# U_LEDs_I2C_PORT.net
KiCad netlist of a schematic drawn in Altium Designer
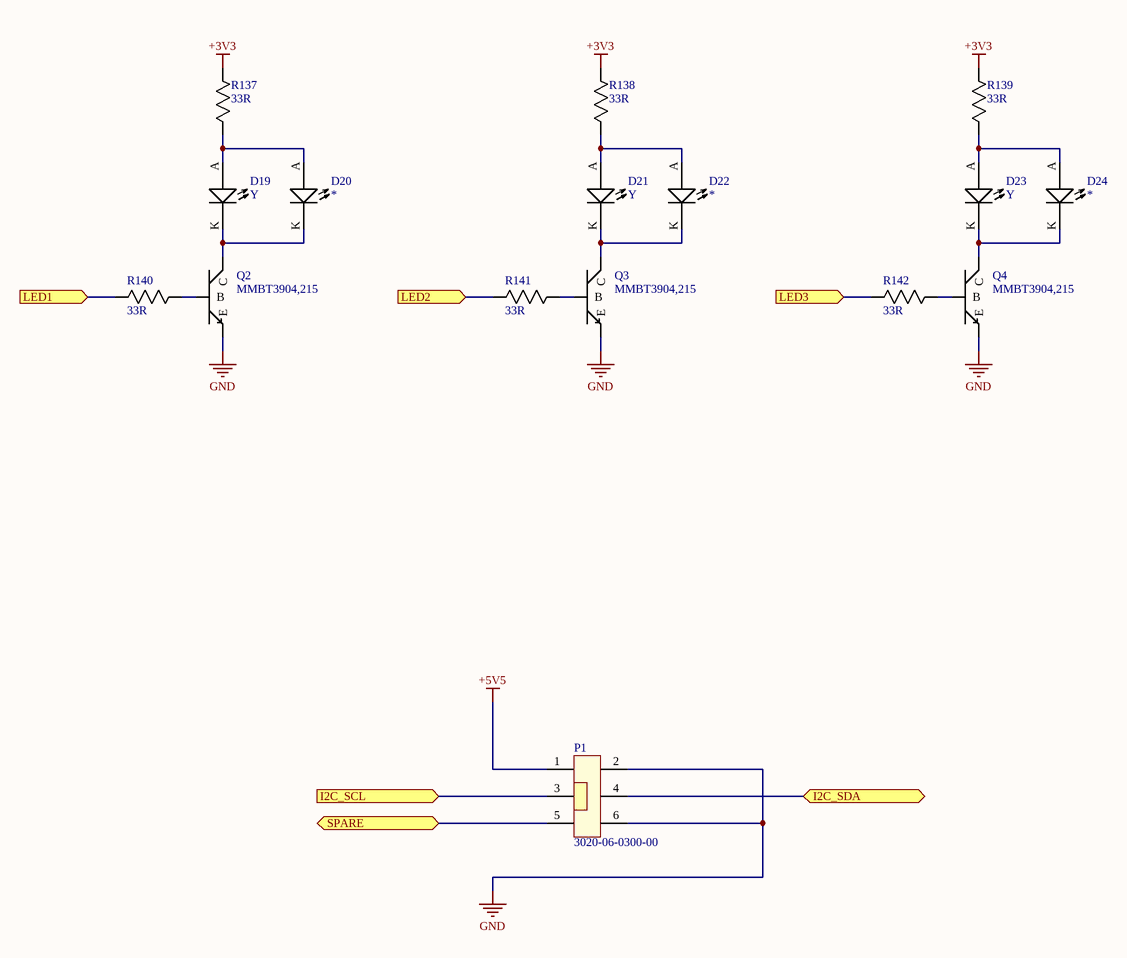
[diagram p0: U_LEDs_I2C_PORT.SchDoc]

(export (version "E")
  (design (tool "Eeschema 10.0.6"))
  (components
    (comp (ref "D19")
      (value "Diode_LED")
      (footprint "0805_LED")
      (description "LED")
      (fields (field (name "MFG") "Osram") (field (name "TYPE") "Y"))
      (libsource (lib "ADAPTONE_CARTE_DE_SON") (part "Diode_LED"))
    )
    (comp (ref "D20")
      (value "Diode_LED")
      (footprint "0805_LED")
      (description "LED")
      (fields (field (name "MFG") "Osram") (field (name "NI") "*"))
      (libsource (lib "ADAPTONE_CARTE_DE_SON") (part "Diode_LED"))
    )
    (comp (ref "D21")
      (value "Diode_LED")
      (footprint "0805_LED")
      (description "LED")
      (fields (field (name "MFG") "Osram") (field (name "TYPE") "Y"))
      (libsource (lib "ADAPTONE_CARTE_DE_SON") (part "Diode_LED"))
    )
    (comp (ref "D22")
      (value "Diode_LED")
      (footprint "0805_LED")
      (description "LED")
      (fields (field (name "MFG") "Osram") (field (name "NI") "*"))
      (libsource (lib "ADAPTONE_CARTE_DE_SON") (part "Diode_LED"))
    )
    (comp (ref "D23")
      (value "Diode_LED")
      (footprint "0805_LED")
      (description "LED")
      (fields (field (name "MFG") "Osram") (field (name "TYPE") "Y"))
      (libsource (lib "ADAPTONE_CARTE_DE_SON") (part "Diode_LED"))
    )
    (comp (ref "D24")
      (value "Diode_LED")
      (footprint "0805_LED")
      (description "LED")
      (fields (field (name "MFG") "Osram") (field (name "NI") "*"))
      (libsource (lib "ADAPTONE_CARTE_DE_SON") (part "Diode_LED"))
    )
    (comp (ref "P1")
      (value "CON6_3020-06-0300-00")
      (footprint "CONN6_100mils_pol_SMD")
      (description "6-pins")
      (fields (field (name "MFG") "Harwin") (field (name "MFG_PN") "3020-06-0300-00"))
      (libsource (lib "ADAPTONE_CARTE_DE_SON") (part "CON6_3020-06-0300-00"))
    )
    (comp (ref "Q2")
      (value "BJT_N_GDS")
      (footprint "SOT23_GDS")
      (description "BJT NPN")
      (fields (field (name "MFG") "NXP") (field (name "MFG_PN") "MMBT3904,215"))
      (libsource (lib "ADAPTONE_CARTE_DE_SON") (part "BJT_N_GDS"))
    )
    (comp (ref "Q3")
      (value "BJT_N_GDS")
      (footprint "SOT23_GDS")
      (description "BJT NPN")
      (fields (field (name "MFG") "NXP") (field (name "MFG_PN") "MMBT3904,215"))
      (libsource (lib "ADAPTONE_CARTE_DE_SON") (part "BJT_N_GDS"))
    )
    (comp (ref "Q4")
      (value "BJT_N_GDS")
      (footprint "SOT23_GDS")
      (description "BJT NPN")
      (fields (field (name "MFG") "NXP") (field (name "MFG_PN") "MMBT3904,215"))
      (libsource (lib "ADAPTONE_CARTE_DE_SON") (part "BJT_N_GDS"))
    )
    (comp (ref "R137")
      (value "33R")
      (footprint "0603")
      (description "Resistor")
      (fields (field (name "MFG") "Yageo"))
      (libsource (lib "ADAPTONE_CARTE_DE_SON") (part "Resistor"))
    )
    (comp (ref "R138")
      (value "33R")
      (footprint "0603")
      (description "Resistor")
      (fields (field (name "MFG") "Yageo"))
      (libsource (lib "ADAPTONE_CARTE_DE_SON") (part "Resistor"))
    )
    (comp (ref "R139")
      (value "33R")
      (footprint "0603")
      (description "Resistor")
      (fields (field (name "MFG") "Yageo"))
      (libsource (lib "ADAPTONE_CARTE_DE_SON") (part "Resistor"))
    )
    (comp (ref "R140")
      (value "33R")
      (footprint "0603")
      (description "Resistor")
      (fields (field (name "MFG") "Yageo"))
      (libsource (lib "ADAPTONE_CARTE_DE_SON") (part "Resistor"))
    )
    (comp (ref "R141")
      (value "33R")
      (footprint "0603")
      (description "Resistor")
      (fields (field (name "MFG") "Yageo"))
      (libsource (lib "ADAPTONE_CARTE_DE_SON") (part "Resistor"))
    )
    (comp (ref "R142")
      (value "33R")
      (footprint "0603")
      (description "Resistor")
      (fields (field (name "MFG") "Yageo"))
      (libsource (lib "ADAPTONE_CARTE_DE_SON") (part "Resistor"))
    )
  )
  (nets
    (net (code "1") (name "+3V3") (class "Default")
      (node (ref "R137") (pin "2") (pintype "passive"))
      (node (ref "R138") (pin "2") (pintype "passive"))
      (node (ref "R139") (pin "2") (pintype "passive"))
    )
    (net (code "2") (name "+5V5") (class "Default") (node (ref "P1") (pin "1") (pintype "passive")))
    (net (code "3") (name "/I2C_SCL") (class "Default") (node (ref "P1") (pin "3") (pintype "passive")))
    (net (code "4") (name "/I2C_SDA") (class "Default") (node (ref "P1") (pin "4") (pintype "passive")))
    (net (code "5") (name "/LED1") (class "Default") (node (ref "R140") (pin "1") (pintype "passive")))
    (net (code "6") (name "/LED2") (class "Default") (node (ref "R141") (pin "1") (pintype "passive")))
    (net (code "7") (name "/LED3") (class "Default") (node (ref "R142") (pin "1") (pintype "passive")))
    (net (code "8") (name "/SPARE") (class "Default") (node (ref "P1") (pin "5") (pintype "passive")))
    (net (code "9") (name "GND") (class "Default")
      (node (ref "P1") (pin "2") (pintype "passive"))
      (node (ref "P1") (pin "6") (pintype "passive"))
      (node (ref "Q2") (pin "S") (pinfunction "E_S") (pintype "passive"))
      (node (ref "Q3") (pin "S") (pinfunction "E_S") (pintype "passive"))
      (node (ref "Q4") (pin "S") (pinfunction "E_S") (pintype "passive"))
    )
    (net (code "10") (name "Net-(D19-PadA)") (class "Default")
      (node (ref "D19") (pin "A") (pintype "passive"))
      (node (ref "D20") (pin "A") (pintype "passive"))
      (node (ref "R137") (pin "1") (pintype "passive"))
    )
    (net (code "11") (name "Net-(D21-PadA)") (class "Default")
      (node (ref "D21") (pin "A") (pintype "passive"))
      (node (ref "D22") (pin "A") (pintype "passive"))
      (node (ref "R138") (pin "1") (pintype "passive"))
    )
    (net (code "12") (name "Net-(D23-PadA)") (class "Default")
      (node (ref "D23") (pin "A") (pintype "passive"))
      (node (ref "D24") (pin "A") (pintype "passive"))
      (node (ref "R139") (pin "1") (pintype "passive"))
    )
    (net (code "13") (name "Net-(Q2-B)") (class "Default")
      (node (ref "Q2") (pin "G") (pinfunction "B_G") (pintype "passive"))
      (node (ref "R140") (pin "2") (pintype "passive"))
    )
    (net (code "14") (name "Net-(Q2-C)") (class "Default")
      (node (ref "D19") (pin "K") (pintype "passive"))
      (node (ref "D20") (pin "K") (pintype "passive"))
      (node (ref "Q2") (pin "D") (pinfunction "C_D") (pintype "passive"))
    )
    (net (code "15") (name "Net-(Q3-B)") (class "Default")
      (node (ref "Q3") (pin "G") (pinfunction "B_G") (pintype "passive"))
      (node (ref "R141") (pin "2") (pintype "passive"))
    )
    (net (code "16") (name "Net-(Q3-C)") (class "Default")
      (node (ref "D21") (pin "K") (pintype "passive"))
      (node (ref "D22") (pin "K") (pintype "passive"))
      (node (ref "Q3") (pin "D") (pinfunction "C_D") (pintype "passive"))
    )
    (net (code "17") (name "Net-(Q4-B)") (class "Default")
      (node (ref "Q4") (pin "G") (pinfunction "B_G") (pintype "passive"))
      (node (ref "R142") (pin "2") (pintype "passive"))
    )
    (net (code "18") (name "Net-(Q4-C)") (class "Default")
      (node (ref "D23") (pin "K") (pintype "passive"))
      (node (ref "D24") (pin "K") (pintype "passive"))
      (node (ref "Q4") (pin "D") (pinfunction "C_D") (pintype "passive"))
    )
  )
)
